# tribometer-adc.net
KiCad netlist of a schematic drawn in EAGLE
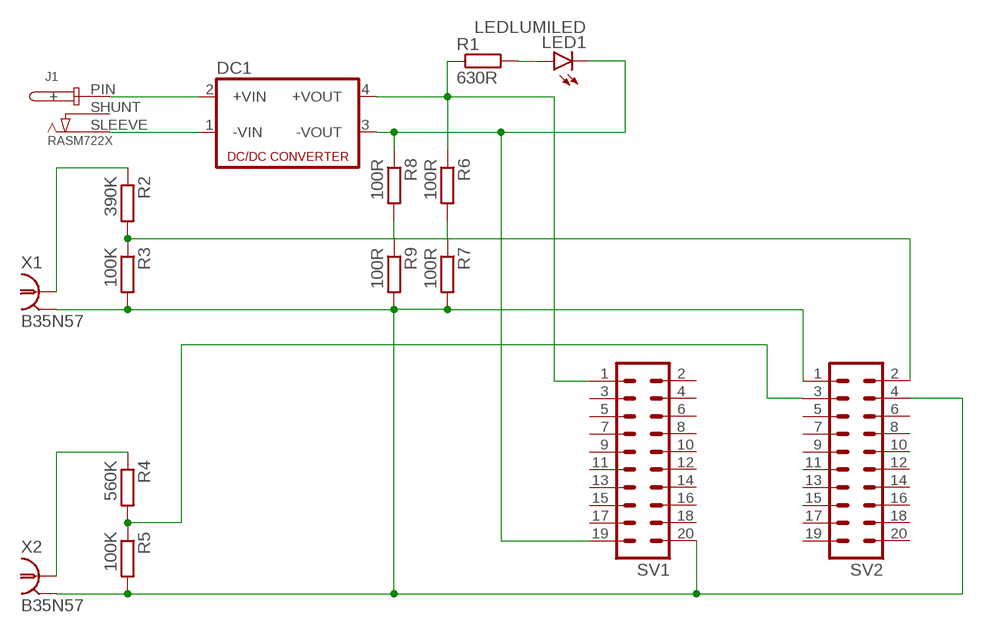
[diagram p0: schematic, sheet 1]

(export (version "E")
  (design (tool "Eeschema 10.0.6"))
  (components
    (comp (ref "DC1")
      (value "NME")
      (footprint "eagle-import:NME")
      (fields (field (name "MF") "C & D TECHNOLOGIES, INC") (field (name "MPN") "NME1205D"))
      (libsource (lib "eagle-import") (part "NME"))
    )
    (comp (ref "J1")
      (value "RASM722X")
      (footprint "eagle-import:RASM722X")
      (fields
        (field (name "DIGI-KEY_PART_NO") "RASM722X-ND")
        (field (name "MANUFACTURER") "Switchcraft Inc.")
        (field (name "CREATED_BY") " PCBLayout.com")
      )
      (libsource (lib "eagle-import") (part "RASM722X"))
    )
    (comp (ref "LED1")
      (value "LEDLUMILED")
      (footprint "eagle-import:LUMILED")
      (libsource (lib "eagle-import") (part "LEDLUMILED"))
    )
    (comp (ref "R1")
      (value "630R")
      (footprint "eagle-import:0207_12")
      (libsource (lib "eagle-import") (part "R-EU_0207/12"))
    )
    (comp (ref "R2")
      (value "390K")
      (footprint "eagle-import:0207_12")
      (libsource (lib "eagle-import") (part "R-EU_0207/12"))
    )
    (comp (ref "R3")
      (value "100K")
      (footprint "eagle-import:0207_12")
      (libsource (lib "eagle-import") (part "R-EU_0207/12"))
    )
    (comp (ref "R4")
      (value "560K")
      (footprint "eagle-import:0207_12")
      (libsource (lib "eagle-import") (part "R-EU_0207/12"))
    )
    (comp (ref "R5")
      (value "100K")
      (footprint "eagle-import:0207_12")
      (libsource (lib "eagle-import") (part "R-EU_0207/12"))
    )
    (comp (ref "R6")
      (value "100R")
      (footprint "eagle-import:0207_12")
      (libsource (lib "eagle-import") (part "R-EU_0207/12"))
    )
    (comp (ref "R7")
      (value "100R")
      (footprint "eagle-import:0207_12")
      (libsource (lib "eagle-import") (part "R-EU_0207/12"))
    )
    (comp (ref "R8")
      (value "100R")
      (footprint "eagle-import:0207_12")
      (libsource (lib "eagle-import") (part "R-EU_0207/12"))
    )
    (comp (ref "R9")
      (value "100R")
      (footprint "eagle-import:0207_12")
      (libsource (lib "eagle-import") (part "R-EU_0207/12"))
    )
    (comp (ref "SV1")
      (value "MA10-2")
      (footprint "eagle-import:MA10-2")
      (libsource (lib "eagle-import") (part "MA10-2"))
    )
    (comp (ref "SV2")
      (value "MA10-2")
      (footprint "eagle-import:MA10-2")
      (libsource (lib "eagle-import") (part "MA10-2"))
    )
    (comp (ref "X1")
      (value "B35N57")
      (footprint "eagle-import:B35N57")
      (libsource (lib "eagle-import") (part "B35N57"))
    )
    (comp (ref "X2")
      (value "B35N57")
      (footprint "eagle-import:B35N57")
      (libsource (lib "eagle-import") (part "B35N57"))
    )
  )
  (nets
    (net (code "1") (name "Net-(DC1-+VIN)") (class "Default")
      (node (ref "DC1") (pin "2") (pinfunction "+VIN_2") (pintype "passive"))
      (node (ref "J1") (pin "PIN") (pinfunction "+_PIN") (pintype "passive"))
    )
    (net (code "2") (name "Net-(DC1-+VOUT)") (class "Default")
      (node (ref "DC1") (pin "4") (pinfunction "+VOUT_4") (pintype "passive"))
      (node (ref "R1") (pin "1") (pinfunction "1_1") (pintype "passive"))
      (node (ref "R6") (pin "1") (pinfunction "1_1") (pintype "passive"))
      (node (ref "SV1") (pin "1") (pinfunction "1_1") (pintype "passive"))
    )
    (net (code "3") (name "Net-(DC1--VIN)") (class "Default")
      (node (ref "DC1") (pin "1") (pinfunction "-VIN_1") (pintype "passive"))
      (node (ref "J1") (pin "SLEEVE") (pinfunction "NEG_SLEEVE") (pintype "passive"))
    )
    (net (code "4") (name "Net-(DC1--VOUT)") (class "Default")
      (node (ref "DC1") (pin "3") (pinfunction "-VOUT_3") (pintype "passive"))
      (node (ref "LED1") (pin "4-") (pinfunction "C_4-") (pintype "passive"))
      (node (ref "R8") (pin "1") (pinfunction "1_1") (pintype "passive"))
      (node (ref "SV1") (pin "19") (pinfunction "19_19") (pintype "passive"))
    )
    (net (code "5") (name "Net-(LED1-A)") (class "Default")
      (node (ref "LED1") (pin "2+") (pinfunction "A_2+") (pintype "passive"))
      (node (ref "R1") (pin "2") (pinfunction "2_2") (pintype "passive"))
    )
    (net (code "6") (name "Net-(R2-Pad1)") (class "Default")
      (node (ref "R2") (pin "1") (pinfunction "1_1") (pintype "passive"))
      (node (ref "X1") (pin "1") (pinfunction "1_1") (pintype "passive"))
    )
    (net (code "7") (name "Net-(R2-Pad2)") (class "Default")
      (node (ref "R2") (pin "2") (pinfunction "2_2") (pintype "passive"))
      (node (ref "R3") (pin "1") (pinfunction "1_1") (pintype "passive"))
      (node (ref "SV2") (pin "2") (pinfunction "2_2") (pintype "passive"))
    )
    (net (code "8") (name "Net-(R3-Pad2)") (class "Default")
      (node (ref "R3") (pin "2") (pinfunction "2_2") (pintype "passive"))
      (node (ref "R5") (pin "2") (pinfunction "2_2") (pintype "passive"))
      (node (ref "R7") (pin "2") (pinfunction "2_2") (pintype "passive"))
      (node (ref "R9") (pin "2") (pinfunction "2_2") (pintype "passive"))
      (node (ref "SV1") (pin "20") (pinfunction "20_20") (pintype "passive"))
      (node (ref "SV2") (pin "1") (pinfunction "1_1") (pintype "passive"))
      (node (ref "SV2") (pin "4") (pinfunction "4_4") (pintype "passive"))
      (node (ref "X1") (pin "2") (pinfunction "2_2") (pintype "passive"))
      (node (ref "X1") (pin "3") (pinfunction "2_3") (pintype "passive"))
      (node (ref "X1") (pin "4") (pinfunction "2_4") (pintype "passive"))
      (node (ref "X1") (pin "5") (pinfunction "2_5") (pintype "passive"))
      (node (ref "X2") (pin "2") (pinfunction "2_2") (pintype "passive"))
      (node (ref "X2") (pin "3") (pinfunction "2_3") (pintype "passive"))
      (node (ref "X2") (pin "4") (pinfunction "2_4") (pintype "passive"))
      (node (ref "X2") (pin "5") (pinfunction "2_5") (pintype "passive"))
    )
    (net (code "9") (name "Net-(R4-Pad1)") (class "Default")
      (node (ref "R4") (pin "1") (pinfunction "1_1") (pintype "passive"))
      (node (ref "X2") (pin "1") (pinfunction "1_1") (pintype "passive"))
    )
    (net (code "10") (name "Net-(R4-Pad2)") (class "Default")
      (node (ref "R4") (pin "2") (pinfunction "2_2") (pintype "passive"))
      (node (ref "R5") (pin "1") (pinfunction "1_1") (pintype "passive"))
      (node (ref "SV2") (pin "3") (pinfunction "3_3") (pintype "passive"))
    )
    (net (code "11") (name "Net-(R6-Pad2)") (class "Default")
      (node (ref "R6") (pin "2") (pinfunction "2_2") (pintype "passive"))
      (node (ref "R7") (pin "1") (pinfunction "1_1") (pintype "passive"))
    )
    (net (code "12") (name "Net-(R8-Pad2)") (class "Default")
      (node (ref "R8") (pin "2") (pinfunction "2_2") (pintype "passive"))
      (node (ref "R9") (pin "1") (pinfunction "1_1") (pintype "passive"))
    )
    (net (code "13") (name "unconnected-(J1---PadSHUNT)") (class "Default")
      (node (ref "J1") (pin "SHUNT") (pinfunction "-_SHUNT") (pintype "passive"))
    )
    (net (code "14") (name "unconnected-(SV1-Pad2)") (class "Default")
      (node (ref "SV1") (pin "2") (pinfunction "2_2") (pintype "passive"))
    )
    (net (code "15") (name "unconnected-(SV1-Pad3)") (class "Default")
      (node (ref "SV1") (pin "3") (pinfunction "3_3") (pintype "passive"))
    )
    (net (code "16") (name "unconnected-(SV1-Pad4)") (class "Default")
      (node (ref "SV1") (pin "4") (pinfunction "4_4") (pintype "passive"))
    )
    (net (code "17") (name "unconnected-(SV1-Pad5)") (class "Default")
      (node (ref "SV1") (pin "5") (pinfunction "5_5") (pintype "passive"))
    )
    (net (code "18") (name "unconnected-(SV1-Pad6)") (class "Default")
      (node (ref "SV1") (pin "6") (pinfunction "6_6") (pintype "passive"))
    )
    (net (code "19") (name "unconnected-(SV1-Pad7)") (class "Default")
      (node (ref "SV1") (pin "7") (pinfunction "7_7") (pintype "passive"))
    )
    (net (code "20") (name "unconnected-(SV1-Pad8)") (class "Default")
      (node (ref "SV1") (pin "8") (pinfunction "8_8") (pintype "passive"))
    )
    (net (code "21") (name "unconnected-(SV1-Pad9)") (class "Default")
      (node (ref "SV1") (pin "9") (pinfunction "9_9") (pintype "passive"))
    )
    (net (code "22") (name "unconnected-(SV1-Pad10)") (class "Default")
      (node (ref "SV1") (pin "10") (pinfunction "10_10") (pintype "passive"))
    )
    (net (code "23") (name "unconnected-(SV1-Pad11)") (class "Default")
      (node (ref "SV1") (pin "11") (pinfunction "11_11") (pintype "passive"))
    )
    (net (code "24") (name "unconnected-(SV1-Pad12)") (class "Default")
      (node (ref "SV1") (pin "12") (pinfunction "12_12") (pintype "passive"))
    )
    (net (code "25") (name "unconnected-(SV1-Pad13)") (class "Default")
      (node (ref "SV1") (pin "13") (pinfunction "13_13") (pintype "passive"))
    )
    (net (code "26") (name "unconnected-(SV1-Pad14)") (class "Default")
      (node (ref "SV1") (pin "14") (pinfunction "14_14") (pintype "passive"))
    )
    (net (code "27") (name "unconnected-(SV1-Pad15)") (class "Default")
      (node (ref "SV1") (pin "15") (pinfunction "15_15") (pintype "passive"))
    )
    (net (code "28") (name "unconnected-(SV1-Pad16)") (class "Default")
      (node (ref "SV1") (pin "16") (pinfunction "16_16") (pintype "passive"))
    )
    (net (code "29") (name "unconnected-(SV1-Pad17)") (class "Default")
      (node (ref "SV1") (pin "17") (pinfunction "17_17") (pintype "passive"))
    )
    (net (code "30") (name "unconnected-(SV1-Pad18)") (class "Default")
      (node (ref "SV1") (pin "18") (pinfunction "18_18") (pintype "passive"))
    )
    (net (code "31") (name "unconnected-(SV2-Pad5)") (class "Default")
      (node (ref "SV2") (pin "5") (pinfunction "5_5") (pintype "passive"))
    )
    (net (code "32") (name "unconnected-(SV2-Pad6)") (class "Default")
      (node (ref "SV2") (pin "6") (pinfunction "6_6") (pintype "passive"))
    )
    (net (code "33") (name "unconnected-(SV2-Pad7)") (class "Default")
      (node (ref "SV2") (pin "7") (pinfunction "7_7") (pintype "passive"))
    )
    (net (code "34") (name "unconnected-(SV2-Pad8)") (class "Default")
      (node (ref "SV2") (pin "8") (pinfunction "8_8") (pintype "passive"))
    )
    (net (code "35") (name "unconnected-(SV2-Pad9)") (class "Default")
      (node (ref "SV2") (pin "9") (pinfunction "9_9") (pintype "passive"))
    )
    (net (code "36") (name "unconnected-(SV2-Pad10)") (class "Default")
      (node (ref "SV2") (pin "10") (pinfunction "10_10") (pintype "passive"))
    )
    (net (code "37") (name "unconnected-(SV2-Pad11)") (class "Default")
      (node (ref "SV2") (pin "11") (pinfunction "11_11") (pintype "passive"))
    )
    (net (code "38") (name "unconnected-(SV2-Pad12)") (class "Default")
      (node (ref "SV2") (pin "12") (pinfunction "12_12") (pintype "passive"))
    )
    (net (code "39") (name "unconnected-(SV2-Pad13)") (class "Default")
      (node (ref "SV2") (pin "13") (pinfunction "13_13") (pintype "passive"))
    )
    (net (code "40") (name "unconnected-(SV2-Pad14)") (class "Default")
      (node (ref "SV2") (pin "14") (pinfunction "14_14") (pintype "passive"))
    )
    (net (code "41") (name "unconnected-(SV2-Pad15)") (class "Default")
      (node (ref "SV2") (pin "15") (pinfunction "15_15") (pintype "passive"))
    )
    (net (code "42") (name "unconnected-(SV2-Pad16)") (class "Default")
      (node (ref "SV2") (pin "16") (pinfunction "16_16") (pintype "passive"))
    )
    (net (code "43") (name "unconnected-(SV2-Pad17)") (class "Default")
      (node (ref "SV2") (pin "17") (pinfunction "17_17") (pintype "passive"))
    )
    (net (code "44") (name "unconnected-(SV2-Pad18)") (class "Default")
      (node (ref "SV2") (pin "18") (pinfunction "18_18") (pintype "passive"))
    )
    (net (code "45") (name "unconnected-(SV2-Pad19)") (class "Default")
      (node (ref "SV2") (pin "19") (pinfunction "19_19") (pintype "passive"))
    )
    (net (code "46") (name "unconnected-(SV2-Pad20)") (class "Default")
      (node (ref "SV2") (pin "20") (pinfunction "20_20") (pintype "passive"))
    )
  )
)
